# PP4_pD_GND.net
KiCad netlist of a schematic drawn in Altium Designer
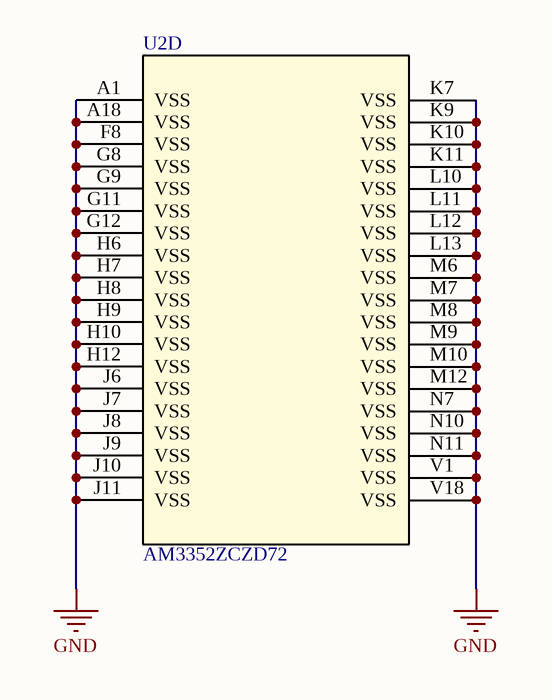
[diagram p0: PP4_pD_GND.SchDoc]

(export (version "E")
  (design (tool "Eeschema 10.0.6"))
  (components
    (comp (ref "U2")
      (value "AM3352ZCZD72")
      (footprint "ZCZ324")
      (description "Microprocesseur ARM")
      (libsource (lib "Michel") (part "AM3352BZCZD80"))
    )
  )
  (nets
    (net (code "1") (name "GND") (class "Default")
      (node (ref "U2") (pin "A1") (pinfunction "VSS_A1") (pintype "power_in"))
      (node (ref "U2") (pin "A18") (pinfunction "VSS_A18") (pintype "power_in"))
      (node (ref "U2") (pin "F8") (pinfunction "VSS_F8") (pintype "power_in"))
      (node (ref "U2") (pin "G11") (pinfunction "VSS_G11") (pintype "power_in"))
      (node (ref "U2") (pin "G12") (pinfunction "VSS_G12") (pintype "power_in"))
      (node (ref "U2") (pin "G8") (pinfunction "VSS_G8") (pintype "power_in"))
      (node (ref "U2") (pin "G9") (pinfunction "VSS_G9") (pintype "power_in"))
      (node (ref "U2") (pin "H10") (pinfunction "VSS_H10") (pintype "power_in"))
      (node (ref "U2") (pin "H12") (pinfunction "VSS_H12") (pintype "power_in"))
      (node (ref "U2") (pin "H6") (pinfunction "VSS_H6") (pintype "power_in"))
      (node (ref "U2") (pin "H7") (pinfunction "VSS_H7") (pintype "power_in"))
      (node (ref "U2") (pin "H8") (pinfunction "VSS_H8") (pintype "power_in"))
      (node (ref "U2") (pin "H9") (pinfunction "VSS_H9") (pintype "power_in"))
      (node (ref "U2") (pin "J10") (pinfunction "VSS_J10") (pintype "power_in"))
      (node (ref "U2") (pin "J11") (pinfunction "VSS_J11") (pintype "power_in"))
      (node (ref "U2") (pin "J6") (pinfunction "VSS_J6") (pintype "power_in"))
      (node (ref "U2") (pin "J7") (pinfunction "VSS_J7") (pintype "power_in"))
      (node (ref "U2") (pin "J8") (pinfunction "VSS_J8") (pintype "power_in"))
      (node (ref "U2") (pin "J9") (pinfunction "VSS_J9") (pintype "power_in"))
      (node (ref "U2") (pin "K10") (pinfunction "VSS_K10") (pintype "power_in"))
      (node (ref "U2") (pin "K11") (pinfunction "VSS_K11") (pintype "power_in"))
      (node (ref "U2") (pin "K7") (pinfunction "VSS_K7") (pintype "power_in"))
      (node (ref "U2") (pin "K9") (pinfunction "VSS_K9") (pintype "power_in"))
      (node (ref "U2") (pin "L10") (pinfunction "VSS_L10") (pintype "power_in"))
      (node (ref "U2") (pin "L11") (pinfunction "VSS_L11") (pintype "power_in"))
      (node (ref "U2") (pin "L12") (pinfunction "VSS_L12") (pintype "power_in"))
      (node (ref "U2") (pin "L13") (pinfunction "VSS_L13") (pintype "power_in"))
      (node (ref "U2") (pin "M10") (pinfunction "VSS_M10") (pintype "power_in"))
      (node (ref "U2") (pin "M12") (pinfunction "VSS_M12") (pintype "power_in"))
      (node (ref "U2") (pin "M6") (pinfunction "VSS_M6") (pintype "power_in"))
      (node (ref "U2") (pin "M7") (pinfunction "VSS_M7") (pintype "power_in"))
      (node (ref "U2") (pin "M8") (pinfunction "VSS_M8") (pintype "power_in"))
      (node (ref "U2") (pin "M9") (pinfunction "VSS_M9") (pintype "power_in"))
      (node (ref "U2") (pin "N10") (pinfunction "VSS_N10") (pintype "power_in"))
      (node (ref "U2") (pin "N11") (pinfunction "VSS_N11") (pintype "power_in"))
      (node (ref "U2") (pin "N7") (pinfunction "VSS_N7") (pintype "power_in"))
      (node (ref "U2") (pin "V1") (pinfunction "VSS_V1") (pintype "power_in"))
      (node (ref "U2") (pin "V18") (pinfunction "VSS_V18") (pintype "power_in"))
    )
  )
)
